# connector_and_other.net
KiCad netlist of a schematic drawn in Altium Designer
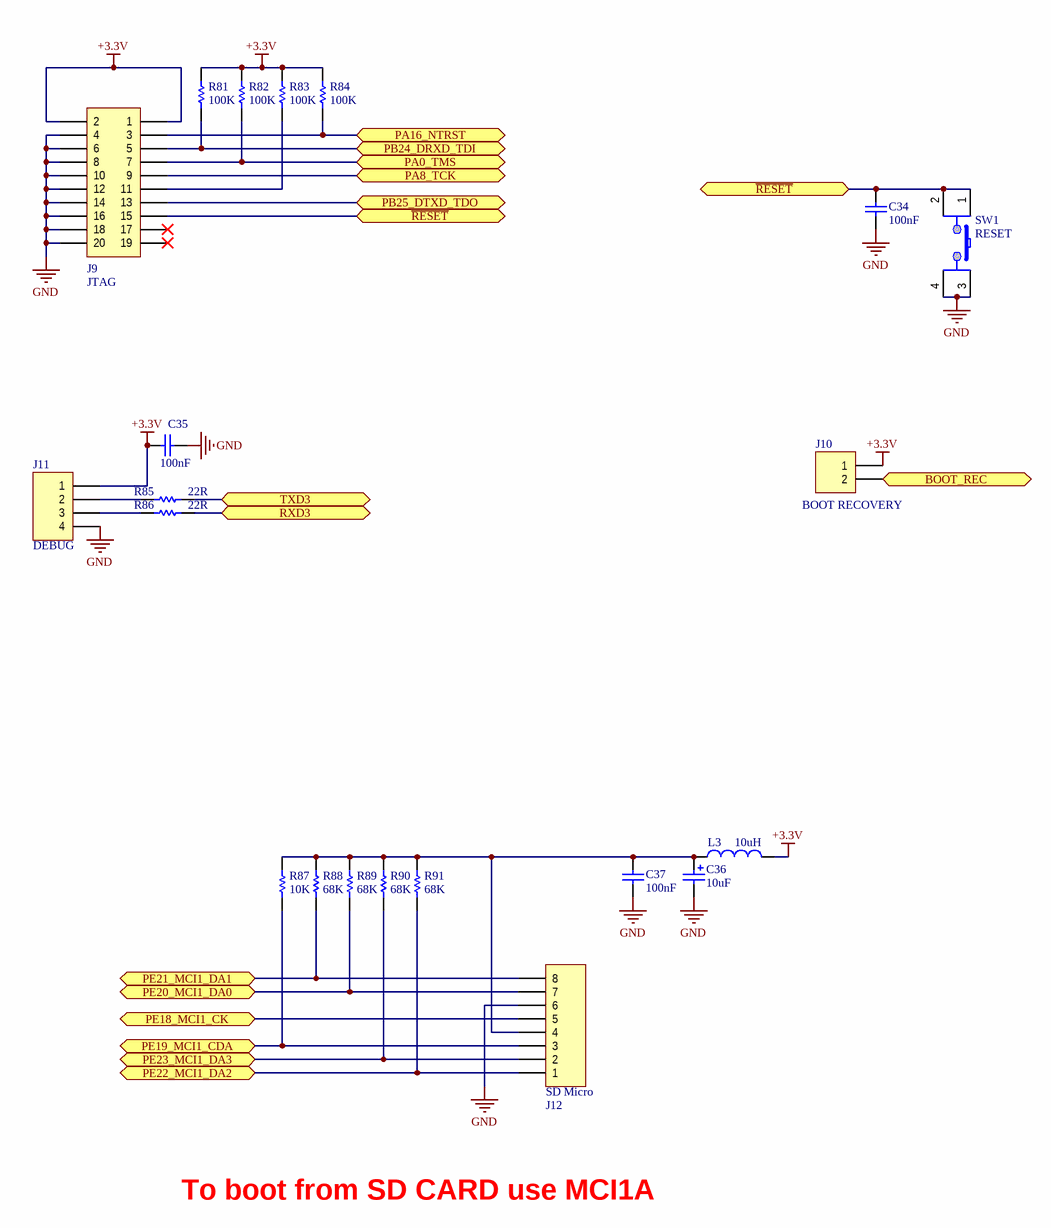
[diagram p0: connector_and_other.SchDoc]

(export (version "E")
  (design (tool "Eeschema 10.0.6"))
  (components
    (comp (ref "C34")
      (value "100nF")
      (footprint "0603_[1608]")
      (description "Ceramic X7R 50V")
      (fields (field (name "PUBLISHER") "Altium Limited"))
      (libsource (lib "DEVELER_Library") (part "Cap"))
    )
    (comp (ref "C35")
      (value "100nF")
      (footprint "0603_[1608]")
      (description "Ceramic X7R 50V")
      (fields (field (name "PUBLISHER") "Altium Limited"))
      (libsource (lib "DEVELER_Library") (part "Cap"))
    )
    (comp (ref "C36")
      (value "10uF")
      (footprint "1206_[3216]")
      (description "Ceramic X5R 25V")
      (fields (field (name "PUBLISHER") "Altium Limited"))
      (libsource (lib "DEVELER_Library") (part "Cap Pol1"))
    )
    (comp (ref "C37")
      (value "100nF")
      (footprint "0603_[1608]")
      (description "Ceramic X7R 50V")
      (fields (field (name "PUBLISHER") "Altium Limited"))
      (libsource (lib "Miscellaneous Devices") (part "Cap"))
    )
    (comp (ref "J9")
      (value "JTAG")
      (footprint "HEADER_2x10_2.54MM_THD")
      (description "Header, 10-Pin, Dual row")
      (fields (field (name "PUBLISHER") "Altium Limited"))
      (libsource (lib "Miscellaneous Connectors") (part "Header 10X2"))
    )
    (comp (ref "J10")
      (value "BOOT RECOVERY")
      (footprint "HEADER_1X2_2.54MM_THD")
      (description "Header, 2-Pin")
      (fields (field (name "PUBLISHER") "Altium Limited"))
      (libsource (lib "Miscellaneous Connectors") (part "Header 2"))
    )
    (comp (ref "J11")
      (value "DEBUG")
      (footprint "HEADER_1X4_2.54MM_THD")
      (description "Header, 4-Pin")
      (fields (field (name "PUBLISHER") "Altium Limited"))
      (libsource (lib "Miscellaneous Connectors") (part "Header 4"))
    )
    (comp (ref "J12")
      (value "SD Micro")
      (footprint "microsd_holder")
      (description "Header, 8-Pin")
      (fields (field (name "PUBLISHER") "Altium Limited"))
      (libsource (lib "Miscellaneous Connectors") (part "Header 8"))
    )
    (comp (ref "L3")
      (value "10uH")
      (footprint "0603_[1608]")
      (description "Inductor (MLZ1608N100L)")
      (fields (field (name "PUBLISHER") "Altium Limited"))
      (libsource (lib "DEVELER_Library") (part "Inductor"))
    )
    (comp (ref "R81")
      (value "100K")
      (footprint "0603_[1608]")
      (description "Resistor")
      (fields (field (name "PUBLISHER") "Altium Limited"))
      (libsource (lib "DEVELER_Library") (part "Res1"))
    )
    (comp (ref "R82")
      (value "100K")
      (footprint "0603_[1608]")
      (description "Resistor")
      (fields (field (name "PUBLISHER") "Altium Limited"))
      (libsource (lib "DEVELER_Library") (part "Res1"))
    )
    (comp (ref "R83")
      (value "100K")
      (footprint "0603_[1608]")
      (description "Resistor")
      (fields (field (name "PUBLISHER") "Altium Limited"))
      (libsource (lib "DEVELER_Library") (part "Res1"))
    )
    (comp (ref "R84")
      (value "100K")
      (footprint "0603_[1608]")
      (description "Resistor")
      (fields (field (name "PUBLISHER") "Altium Limited"))
      (libsource (lib "DEVELER_Library") (part "Res1"))
    )
    (comp (ref "R85")
      (value "22R")
      (footprint "0603_[1608]")
      (description "Resistor")
      (fields (field (name "PUBLISHER") "Altium Limited"))
      (libsource (lib "DEVELER_Library") (part "Res1"))
    )
    (comp (ref "R86")
      (value "22R")
      (footprint "0603_[1608]")
      (description "Resistor")
      (fields (field (name "PUBLISHER") "Altium Limited"))
      (libsource (lib "DEVELER_Library") (part "Res1"))
    )
    (comp (ref "R87")
      (value "10K")
      (footprint "0603_[1608]")
      (description "Resistor")
      (fields (field (name "PUBLISHER") "Altium Limited"))
      (libsource (lib "DEVELER_Library") (part "Res1"))
    )
    (comp (ref "R88")
      (value "68K")
      (footprint "0603_[1608]")
      (description "Resistor")
      (fields (field (name "PUBLISHER") "Altium Limited"))
      (libsource (lib "DEVELER_Library") (part "Res1"))
    )
    (comp (ref "R89")
      (value "68K")
      (footprint "0603_[1608]")
      (description "Resistor")
      (fields (field (name "PUBLISHER") "Altium Limited"))
      (libsource (lib "DEVELER_Library") (part "Res1"))
    )
    (comp (ref "R90")
      (value "68K")
      (footprint "0603_[1608]")
      (description "Resistor")
      (fields (field (name "PUBLISHER") "Altium Limited"))
      (libsource (lib "DEVELER_Library") (part "Res1"))
    )
    (comp (ref "R91")
      (value "68K")
      (footprint "0603_[1608]")
      (description "Resistor")
      (fields (field (name "PUBLISHER") "Altium Limited"))
      (libsource (lib "DEVELER_Library") (part "Res1"))
    )
    (comp (ref "SW1")
      (value "RESET")
      (footprint "TACTILE_SWITCH_6x6MM_SMD")
      (description "Tactile switch")
      (libsource (lib "DEVELER_Library") (part "tactile_switch"))
    )
  )
  (nets
    (net (code "1") (name "+3.3V") (class "Default")
      (node (ref "C35") (pin "1") (pinfunction "1_1") (pintype "passive"))
      (node (ref "J10") (pin "1") (pinfunction "1_1") (pintype "passive"))
      (node (ref "J11") (pin "1") (pinfunction "1_1") (pintype "passive"))
      (node (ref "J9") (pin "1") (pinfunction "1_1") (pintype "passive"))
      (node (ref "J9") (pin "2") (pinfunction "2_2") (pintype "passive"))
      (node (ref "L3") (pin "2") (pinfunction "2_2") (pintype "passive"))
      (node (ref "R81") (pin "1") (pinfunction "1_1") (pintype "passive"))
      (node (ref "R82") (pin "1") (pinfunction "1_1") (pintype "passive"))
      (node (ref "R83") (pin "1") (pinfunction "1_1") (pintype "passive"))
      (node (ref "R84") (pin "1") (pinfunction "1_1") (pintype "passive"))
    )
    (net (code "2") (name "/BOOT_REC") (class "Default")
      (node (ref "J10") (pin "2") (pinfunction "2_2") (pintype "passive"))
    )
    (net (code "3") (name "/PA0_TMS") (class "Default")
      (node (ref "J9") (pin "7") (pinfunction "7_7") (pintype "passive"))
      (node (ref "R82") (pin "2") (pinfunction "2_2") (pintype "passive"))
    )
    (net (code "4") (name "/PA8_TCK") (class "Default")
      (node (ref "J9") (pin "9") (pinfunction "9_9") (pintype "passive"))
    )
    (net (code "5") (name "/PA16_NTRST") (class "Default")
      (node (ref "J9") (pin "3") (pinfunction "3_3") (pintype "passive"))
      (node (ref "R84") (pin "2") (pinfunction "2_2") (pintype "passive"))
    )
    (net (code "6") (name "/PB24_DRXD_TDI") (class "Default")
      (node (ref "J9") (pin "5") (pinfunction "5_5") (pintype "passive"))
      (node (ref "R81") (pin "2") (pinfunction "2_2") (pintype "passive"))
    )
    (net (code "7") (name "/PB25_DTXD_TDO") (class "Default")
      (node (ref "J9") (pin "13") (pinfunction "13_13") (pintype "passive"))
    )
    (net (code "8") (name "/PE18_MCI1_CK") (class "Default")
      (node (ref "J12") (pin "5") (pinfunction "5_5") (pintype "passive"))
    )
    (net (code "9") (name "/PE19_MCI1_CDA") (class "Default")
      (node (ref "J12") (pin "3") (pinfunction "3_3") (pintype "passive"))
      (node (ref "R87") (pin "2") (pinfunction "2_2") (pintype "passive"))
    )
    (net (code "10") (name "/PE20_MCI1_DA0") (class "Default")
      (node (ref "J12") (pin "7") (pinfunction "7_7") (pintype "passive"))
      (node (ref "R89") (pin "2") (pinfunction "2_2") (pintype "passive"))
    )
    (net (code "11") (name "/PE21_MCI1_DA1") (class "Default")
      (node (ref "J12") (pin "8") (pinfunction "8_8") (pintype "passive"))
      (node (ref "R88") (pin "2") (pinfunction "2_2") (pintype "passive"))
    )
    (net (code "12") (name "/PE22_MCI1_DA2") (class "Default")
      (node (ref "J12") (pin "1") (pinfunction "1_1") (pintype "passive"))
      (node (ref "R91") (pin "2") (pinfunction "2_2") (pintype "passive"))
    )
    (net (code "13") (name "/PE23_MCI1_DA3") (class "Default")
      (node (ref "J12") (pin "2") (pinfunction "2_2") (pintype "passive"))
      (node (ref "R90") (pin "2") (pinfunction "2_2") (pintype "passive"))
    )
    (net (code "14") (name "/RESET") (class "Default")
      (node (ref "C34") (pin "2") (pinfunction "2_2") (pintype "passive"))
      (node (ref "J9") (pin "15") (pinfunction "15_15") (pintype "passive"))
      (node (ref "SW1") (pin "1") (pinfunction "1_1") (pintype "passive"))
      (node (ref "SW1") (pin "2") (pinfunction "2_2") (pintype "passive"))
    )
    (net (code "15") (name "/RXD3") (class "Default")
      (node (ref "R86") (pin "1") (pinfunction "1_1") (pintype "passive"))
    )
    (net (code "16") (name "/TXD3") (class "Default")
      (node (ref "R85") (pin "1") (pinfunction "1_1") (pintype "passive"))
    )
    (net (code "17") (name "GND") (class "Default")
      (node (ref "C34") (pin "1") (pinfunction "1_1") (pintype "passive"))
      (node (ref "C35") (pin "2") (pinfunction "2_2") (pintype "passive"))
      (node (ref "C36") (pin "2") (pinfunction "2_2") (pintype "passive"))
      (node (ref "C37") (pin "2") (pinfunction "2_2") (pintype "passive"))
      (node (ref "J11") (pin "4") (pinfunction "4_4") (pintype "passive"))
      (node (ref "J12") (pin "6") (pinfunction "6_6") (pintype "passive"))
      (node (ref "J9") (pin "10") (pinfunction "10_10") (pintype "passive"))
      (node (ref "J9") (pin "12") (pinfunction "12_12") (pintype "passive"))
      (node (ref "J9") (pin "14") (pinfunction "14_14") (pintype "passive"))
      (node (ref "J9") (pin "16") (pinfunction "16_16") (pintype "passive"))
      (node (ref "J9") (pin "18") (pinfunction "18_18") (pintype "passive"))
      (node (ref "J9") (pin "20") (pinfunction "20_20") (pintype "passive"))
      (node (ref "J9") (pin "4") (pinfunction "4_4") (pintype "passive"))
      (node (ref "J9") (pin "6") (pinfunction "6_6") (pintype "passive"))
      (node (ref "J9") (pin "8") (pinfunction "8_8") (pintype "passive"))
      (node (ref "SW1") (pin "3") (pinfunction "3_3") (pintype "passive"))
      (node (ref "SW1") (pin "4") (pinfunction "4_4") (pintype "passive"))
    )
    (net (code "18") (name "Net-(C36-Pad1)") (class "Default")
      (node (ref "C36") (pin "1") (pinfunction "1_1") (pintype "passive"))
      (node (ref "C37") (pin "1") (pinfunction "1_1") (pintype "passive"))
      (node (ref "J12") (pin "4") (pinfunction "4_4") (pintype "passive"))
      (node (ref "L3") (pin "1") (pinfunction "1_1") (pintype "passive"))
      (node (ref "R87") (pin "1") (pinfunction "1_1") (pintype "passive"))
      (node (ref "R88") (pin "1") (pinfunction "1_1") (pintype "passive"))
      (node (ref "R89") (pin "1") (pinfunction "1_1") (pintype "passive"))
      (node (ref "R90") (pin "1") (pinfunction "1_1") (pintype "passive"))
      (node (ref "R91") (pin "1") (pinfunction "1_1") (pintype "passive"))
    )
    (net (code "19") (name "Net-(J9-Pad11)") (class "Default")
      (node (ref "J9") (pin "11") (pinfunction "11_11") (pintype "passive"))
      (node (ref "R83") (pin "2") (pinfunction "2_2") (pintype "passive"))
    )
    (net (code "20") (name "Net-(J11-Pad2)") (class "Default")
      (node (ref "J11") (pin "2") (pinfunction "2_2") (pintype "passive"))
      (node (ref "R85") (pin "2") (pinfunction "2_2") (pintype "passive"))
    )
    (net (code "21") (name "Net-(J11-Pad3)") (class "Default")
      (node (ref "J11") (pin "3") (pinfunction "3_3") (pintype "passive"))
      (node (ref "R86") (pin "2") (pinfunction "2_2") (pintype "passive"))
    )
    (net (code "22") (name "unconnected-(J9-Pad17)") (class "Default")
      (node (ref "J9") (pin "17") (pinfunction "17_17") (pintype "passive+no_connect"))
    )
    (net (code "23") (name "unconnected-(J9-Pad19)") (class "Default")
      (node (ref "J9") (pin "19") (pinfunction "19_19") (pintype "passive+no_connect"))
    )
  )
)
